# power_REG104GA_3V3.net
KiCad netlist of a schematic drawn in Altium Designer
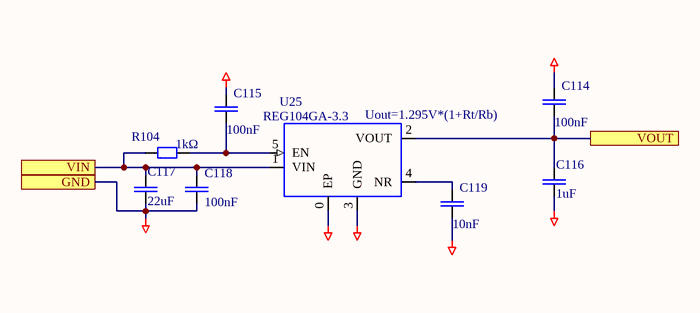
[diagram p0: power_REG104GA_3V3.SchDoc]

(export (version "E")
  (design (tool "Eeschema 10.0.6"))
  (components
    (comp (ref "C114")
      (value "100nF")
      (footprint "CAPC1608N")
      (description "Generic ceramic SMD capacitor")
      (fields (field (name "MAINTAINER") "Evgeniy Kotov"))
      (libsource (lib "[Capacitors] Capacitors SMD") (part "CAPC"))
    )
    (comp (ref "C115")
      (value "100nF")
      (footprint "CAPC1608N")
      (description "Generic ceramic SMD capacitor")
      (fields (field (name "MAINTAINER") "Evgeniy Kotov"))
      (libsource (lib "[Capacitors] Capacitors SMD") (part "CAPC"))
    )
    (comp (ref "C116")
      (value "1uF")
      (footprint "CAPC2012N")
      (description "Generic ceramic SMD capacitor")
      (fields (field (name "MAINTAINER") "Evgeniy Kotov"))
      (libsource (lib "[Capacitors] Capacitors SMD") (part "CAPC"))
    )
    (comp (ref "C117")
      (value "22uF")
      (footprint "CAPC2012N")
      (description "Generic ceramic SMD capacitor")
      (fields (field (name "MAINTAINER") "Evgeniy Kotov"))
      (libsource (lib "[Capacitors] Capacitors SMD") (part "CAPC"))
    )
    (comp (ref "C118")
      (value "100nF")
      (footprint "CAPC1608N")
      (description "Generic ceramic SMD capacitor")
      (fields (field (name "MAINTAINER") "Evgeniy Kotov"))
      (libsource (lib "[Capacitors] Capacitors SMD") (part "CAPC"))
    )
    (comp (ref "C119")
      (value "10nF")
      (footprint "CAPC1608N")
      (description "Generic ceramic SMD capacitor")
      (fields (field (name "MAINTAINER") "Evgeniy Kotov"))
      (libsource (lib "[Capacitors] Capacitors SMD") (part "CAPC"))
    )
    (comp (ref "R104")
      (value "1kΩ")
      (footprint "RESC2012N")
      (description "Resistor, Generic, SMD")
      (fields (field (name "MAINTAINER") "Evgeniy Kotov"))
      (libsource (lib "carrier") (part "RESC"))
    )
    (comp (ref "U25")
      (value "REG104GA-3.3")
      (footprint "SOT223")
      (description "Single Output LDO, 1.0A, Fixed (3.3V), Low Noise, Fast Transient Response")
      (fields
        (field (name "MANUFACTURER") "Texas Instruments")
        (field (name "MANUFACTURER_PART_NUMBER") "reg104-33_dcq_6")
      )
      (libsource (lib "[ICs And Semiconductors] Analog & Interface") (part "REG104GA-3.3"))
    )
  )
  (nets
    (net (code "1") (name "/VIN") (class "Default")
      (node (ref "C117") (pin "2") (pintype "passive"))
      (node (ref "C118") (pin "2") (pintype "passive"))
      (node (ref "R104") (pin "2") (pintype "passive"))
      (node (ref "U25") (pin "1") (pinfunction "VIN_1") (pintype "power_in"))
    )
    (net (code "2") (name "/VOUT") (class "Default")
      (node (ref "C114") (pin "1") (pintype "passive"))
      (node (ref "C116") (pin "2") (pintype "passive"))
      (node (ref "U25") (pin "2") (pinfunction "VOUT_2") (pintype "power_in"))
    )
    (net (code "3") (name "GND") (class "Default")
      (node (ref "C114") (pin "2") (pintype "passive"))
      (node (ref "C115") (pin "2") (pintype "passive"))
      (node (ref "C116") (pin "1") (pintype "passive"))
      (node (ref "C117") (pin "1") (pintype "passive"))
      (node (ref "C118") (pin "1") (pintype "passive"))
      (node (ref "C119") (pin "1") (pintype "passive"))
      (node (ref "U25") (pin "0") (pinfunction "EP_0") (pintype "passive"))
      (node (ref "U25") (pin "3") (pinfunction "GND_3") (pintype "power_in"))
    )
    (net (code "4") (name "Net-(U25-EN)") (class "Default")
      (node (ref "C115") (pin "1") (pintype "passive"))
      (node (ref "R104") (pin "1") (pintype "passive"))
      (node (ref "U25") (pin "5") (pinfunction "EN_5") (pintype "input"))
    )
    (net (code "5") (name "Net-(U25-NR)") (class "Default")
      (node (ref "C119") (pin "2") (pintype "passive"))
      (node (ref "U25") (pin "4") (pinfunction "NR_4") (pintype "passive"))
    )
  )
)
